# greenhouse_MA_3.net
KiCad netlist of a schematic drawn in Altium Designer
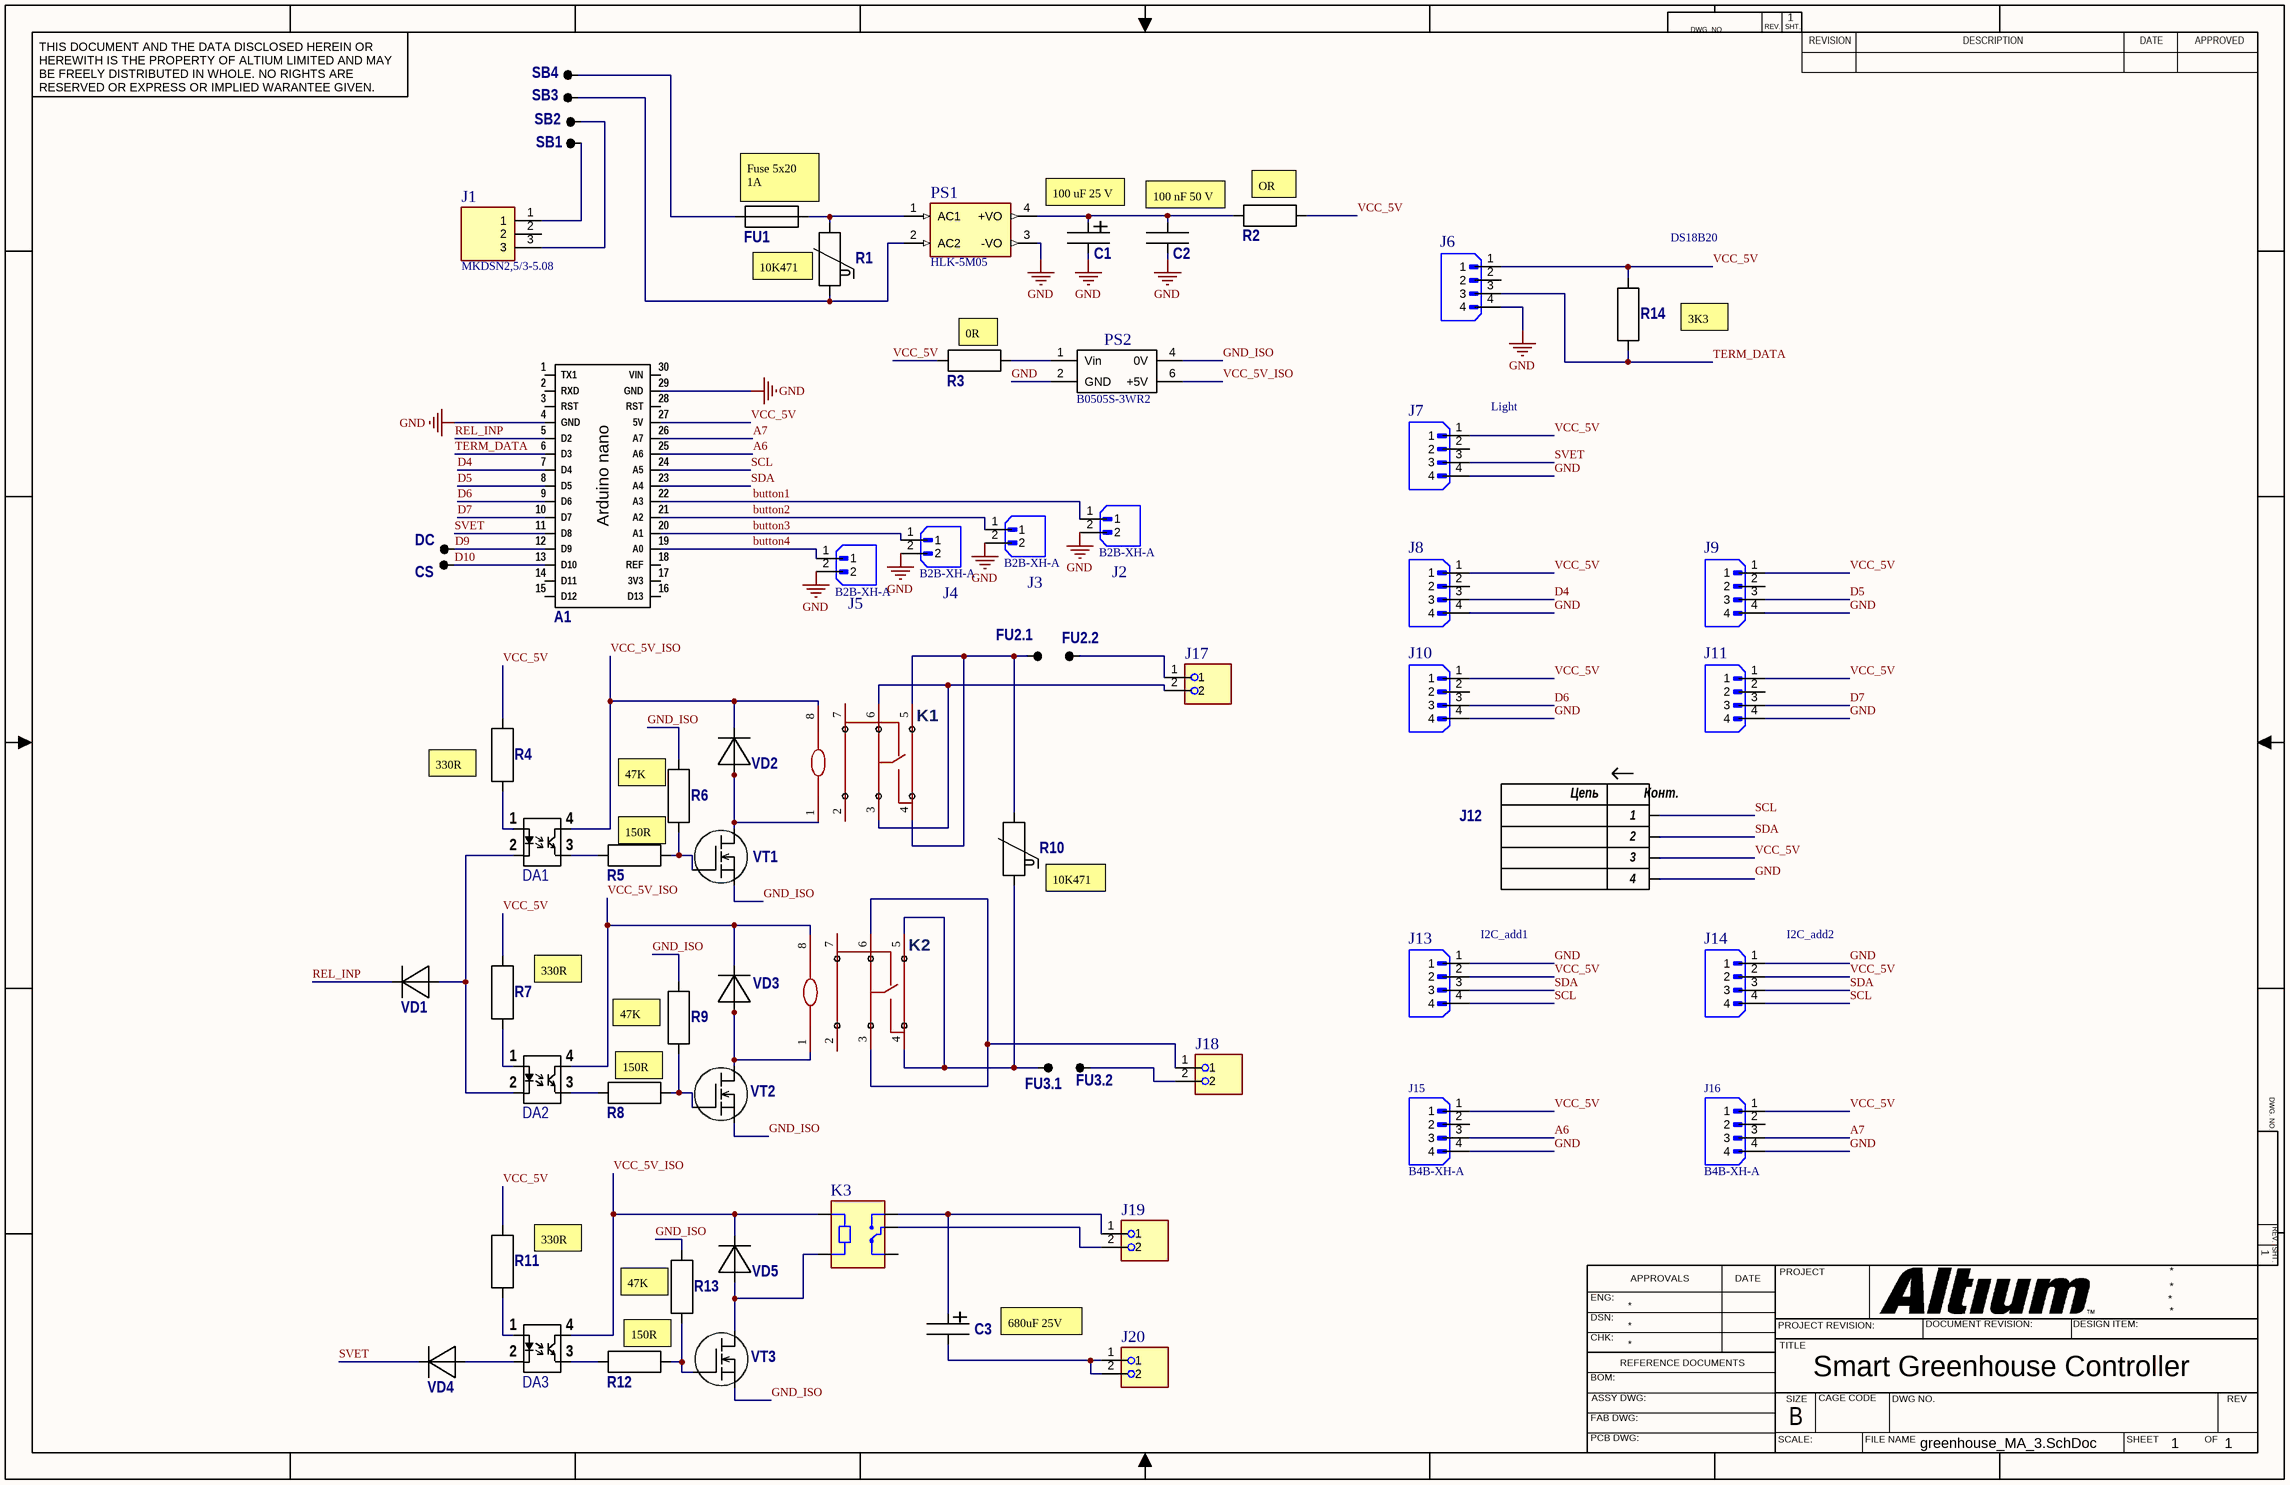
[diagram p0: greenhouse_MA_3.SchDoc]

(export (version "E")
  (design (tool "Eeschema 10.0.6"))
  (components
    (comp (ref "A1")
      (value "Arduino Nano")
      (footprint "Arduino nano")
      (libsource (lib "Microcontroller_V3.4_BVI") (part "Arduino Nano"))
    )
    (comp (ref "C1")
      (value "100uF 25V Electrolytic Capacitor THT Radial")
      (footprint "capr- 2.5D6.5H12")
      (description "Конденсатор алюминиевый радиальный")
      (libsource (lib "RLC V7.1_BVI") (part "C Al R"))
    )
    (comp (ref "C2")
      (value "100nF 50V X7R THT 5mm")
      (footprint "C__s 5-d 5.5-t4")
      (description "Конденсатор керамика")
      (libsource (lib "RLC V7.1_BVI") (part "C_Disk"))
    )
    (comp (ref "C3")
      (value "680uF 25V Electrolytic Capacitor THT Radial")
      (footprint "capr- 3.5D8H20")
      (description "Конденсатор алюминиевый радиальный")
      (libsource (lib "RLC V7.1_BVI") (part "C Al R"))
    )
    (comp (ref "CS")
      (value "Отпайка")
      (footprint "Отпайка 1.2")
      (description "Отпайка для проводника")
      (libsource (lib "RLC V7.1_BVI") (part "Отпайка"))
    )
    (comp (ref "DA1")
      (value "Optocoupler EL817 DIP-4")
      (footprint "DIP-4")
      (description "Оптрон выход - транзистор")
      (libsource (lib "Optocoupler V2.2_BVI") (part "EL817"))
    )
    (comp (ref "DA2")
      (value "Optocoupler EL817 DIP-4")
      (footprint "DIP-4")
      (description "Оптрон выход - транзистор")
      (libsource (lib "Optocoupler V2.2_BVI") (part "EL817"))
    )
    (comp (ref "DA3")
      (value "Optocoupler EL817 DIP-4")
      (footprint "DIP-4")
      (description "Оптрон выход - транзистор")
      (libsource (lib "Optocoupler V2.2_BVI") (part "EL817"))
    )
    (comp (ref "DC")
      (value "Отпайка")
      (footprint "Отпайка 1.2")
      (description "Отпайка для проводника")
      (libsource (lib "RLC V7.1_BVI") (part "Отпайка"))
    )
    (comp (ref "FU1")
      (value "1A slow 5x20 mm")
      (footprint "FU_FC-001-N(DH)")
      (description "Предохранитель плавкий с держателем.")
      (libsource (lib "RLC V7.1_BVI") (part "FU + Clip"))
    )
    (comp (ref "FU2.1")
      (value "Отпайка")
      (footprint "Отпайка 1.5")
      (description "Отпайка для проводника")
      (libsource (lib "RLC V7.1_BVI") (part "Отпайка"))
    )
    (comp (ref "FU2.2")
      (value "Отпайка")
      (footprint "Отпайка 1.5")
      (description "Отпайка для проводника")
      (libsource (lib "RLC V7.1_BVI") (part "Отпайка"))
    )
    (comp (ref "FU3.1")
      (value "Отпайка")
      (footprint "Отпайка 1.5")
      (description "Отпайка для проводника")
      (libsource (lib "RLC V7.1_BVI") (part "Отпайка"))
    )
    (comp (ref "FU3.2")
      (value "Отпайка")
      (footprint "Отпайка 1.5")
      (description "Отпайка для проводника")
      (libsource (lib "RLC V7.1_BVI") (part "Отпайка"))
    )
    (comp (ref "J1")
      (value "MKDSN2,5/3-5.08")
      (footprint "PHOENIX_MKDSN2,5/3-5.08")
      (fields (field (name "MF") "Phoenix Contact"))
      (libsource (lib "MKDSN2_5_3-5.08") (part "MKDSN2,5/3-5.08"))
    )
    (comp (ref "J2")
      (value "B2B-XH-A")
      (footprint "JST_B2B-XH-A")
      (fields (field (name "MF") "{'manufacturer': u'JST Sales America Inc.'}"))
      (libsource (lib "B2B-XH-A") (part "B2B-XH-A"))
    )
    (comp (ref "J3")
      (value "B2B-XH-A")
      (footprint "JST_B2B-XH-A")
      (fields (field (name "MF") "{'manufacturer': u'JST Sales America Inc.'}"))
      (libsource (lib "B2B-XH-A") (part "B2B-XH-A"))
    )
    (comp (ref "J4")
      (value "B2B-XH-A")
      (footprint "JST_B2B-XH-A")
      (fields (field (name "MF") "{'manufacturer': u'JST Sales America Inc.'}"))
      (libsource (lib "B2B-XH-A") (part "B2B-XH-A"))
    )
    (comp (ref "J5")
      (value "B2B-XH-A")
      (footprint "JST_B2B-XH-A")
      (fields (field (name "MF") "{'manufacturer': u'JST Sales America Inc.'}"))
      (libsource (lib "B2B-XH-A") (part "B2B-XH-A"))
    )
    (comp (ref "J6")
      (value "JST B4B-XH-A Connector 1x4 2.5mm THT Vertical")
      (footprint "JST_B4B-XH-A")
      (description "Connector Header Through Hole 4 position 0.098 (2.50mm)")
      (fields (field (name "MF") "JST Sales") (field (name "MP") "B4B-XH-A"))
      (libsource (lib "B4B-XH-A") (part "B4B-XH-A"))
    )
    (comp (ref "J7")
      (value "JST B4B-XH-A Connector 1x4 2.5mm THT Vertical")
      (footprint "JST_B4B-XH-A")
      (description "Connector Header Through Hole 4 position 0.098 (2.50mm)")
      (fields (field (name "MF") "JST Sales") (field (name "MP") "B4B-XH-A"))
      (libsource (lib "B4B-XH-A") (part "B4B-XH-A"))
    )
    (comp (ref "J8")
      (value "JST B4B-XH-A Connector 1x4 2.5mm THT Vertical")
      (footprint "JST_B4B-XH-A")
      (description "Connector Header Through Hole 4 position 0.098 (2.50mm)")
      (fields (field (name "MF") "JST Sales") (field (name "MP") "B4B-XH-A"))
      (libsource (lib "B4B-XH-A") (part "B4B-XH-A"))
    )
    (comp (ref "J9")
      (value "JST B4B-XH-A Connector 1x4 2.5mm THT Vertical")
      (footprint "JST_B4B-XH-A")
      (description "Connector Header Through Hole 4 position 0.098 (2.50mm)")
      (fields (field (name "MF") "JST Sales") (field (name "MP") "B4B-XH-A"))
      (libsource (lib "B4B-XH-A") (part "B4B-XH-A"))
    )
    (comp (ref "J10")
      (value "JST B4B-XH-A Connector 1x4 2.5mm THT Vertical")
      (footprint "JST_B4B-XH-A")
      (description "Connector Header Through Hole 4 position 0.098 (2.50mm)")
      (fields (field (name "MF") "JST Sales") (field (name "MP") "B4B-XH-A"))
      (libsource (lib "B4B-XH-A") (part "B4B-XH-A"))
    )
    (comp (ref "J11")
      (value "JST B4B-XH-A Connector 1x4 2.5mm THT Vertical")
      (footprint "JST_B4B-XH-A")
      (description "Connector Header Through Hole 4 position 0.098 (2.50mm)")
      (fields (field (name "MF") "JST Sales") (field (name "MP") "B4B-XH-A"))
      (libsource (lib "B4B-XH-A") (part "B4B-XH-A"))
    )
    (comp (ref "J12")
      (value "Pin Header 1x4 2.54mm Right Angle THT Male")
      (footprint "KLS1-207-1*04 R")
      (description "Разъём штыревой на плату 2.54мм 1х4 pin")
      (libsource (lib "Connectors V8.3_BVI") (part "Штырь 1* 4  (1)"))
    )
    (comp (ref "J13")
      (value "JST B4B-XH-A Connector 1x4 2.5mm THT Vertical")
      (footprint "JST_B4B-XH-A")
      (description "Connector Header Through Hole 4 position 0.098 (2.50mm)")
      (fields (field (name "MF") "JST Sales") (field (name "MP") "B4B-XH-A"))
      (libsource (lib "B4B-XH-A") (part "B4B-XH-A"))
    )
    (comp (ref "J14")
      (value "JST B4B-XH-A Connector 1x4 2.5mm THT Vertical")
      (footprint "JST_B4B-XH-A")
      (description "Connector Header Through Hole 4 position 0.098 (2.50mm)")
      (fields (field (name "MF") "JST Sales") (field (name "MP") "B4B-XH-A"))
      (libsource (lib "B4B-XH-A") (part "B4B-XH-A"))
    )
    (comp (ref "J15")
      (value "B4B-XH-A")
      (footprint "JST_B4B-XH-A")
      (description "Connector Header Through Hole 4 position 0.098 (2.50mm)")
      (fields (field (name "MF") "JST Sales"))
      (libsource (lib "B4B-XH-A") (part "B4B-XH-A"))
    )
    (comp (ref "J16")
      (value "B4B-XH-A")
      (footprint "JST_B4B-XH-A")
      (description "Connector Header Through Hole 4 position 0.098 (2.50mm)")
      (fields (field (name "MF") "JST Sales"))
      (libsource (lib "B4B-XH-A") (part "B4B-XH-A"))
    )
    (comp (ref "J17")
      (value "Phoenix Contact MKDSN 2,5/2-5.08 Terminal Block 1x2 5.08mm THT")
      (footprint "PHOENIX_1729128")
      (fields (field (name "MF") "Phoenix Contact") (field (name "MP") "1729128"))
      (libsource (lib "MKDSN2_5_2-5.08") (part "1729128"))
    )
    (comp (ref "J18")
      (value "Phoenix Contact MKDSN 2,5/2-5.08 Terminal Block 1x2 5.08mm THT")
      (footprint "PHOENIX_1729128")
      (fields (field (name "MF") "Phoenix Contact") (field (name "MP") "1729128"))
      (libsource (lib "MKDSN2_5_2-5.08") (part "1729128"))
    )
    (comp (ref "J19")
      (value "Phoenix Contact MKDSN 2,5/2-5.08 Terminal Block 1x2 5.08mm THT")
      (footprint "PHOENIX_1729128")
      (fields (field (name "MF") "Phoenix Contact") (field (name "MP") "1729128"))
      (libsource (lib "MKDSN2_5_2-5.08") (part "1729128"))
    )
    (comp (ref "J20")
      (value "Phoenix Contact MKDSN 2,5/2-5.08 Terminal Block 1x2 5.08mm THT")
      (footprint "PHOENIX_1729128")
      (fields (field (name "MF") "Phoenix Contact") (field (name "MP") "1729128"))
      (libsource (lib "MKDSN2_5_2-5.08") (part "1729128"))
    )
    (comp (ref "K1")
      (value "Relay SMIH-05VDC-SL-C 5V 16A THT")
      (footprint "SMIH-5VDC-SL-C")
      (fields (field (name "MANUFACTURER") "松乐") (field (name "MANUFACTURER PART") "SMIH-05VDC-SL-C"))
      (libsource (lib "SMIH-5VDC-SL-C") (part "SMIH-05VDC-SL-C"))
    )
    (comp (ref "K2")
      (value "Relay SMIH-05VDC-SL-C 5V 16A THT")
      (footprint "SMIH-5VDC-SL-C")
      (fields (field (name "MANUFACTURER") "松乐") (field (name "MANUFACTURER PART") "SMIH-05VDC-SL-C"))
      (libsource (lib "SMIH-5VDC-SL-C") (part "SMIH-05VDC-SL-C"))
    )
    (comp (ref "K3")
      (value "Relay SRD-05VDC-SL-C 5V 10A THT")
      (footprint "RELAY_SRD-05VDC-SL-C")
      (fields (field (name "MF") "Songle Relay") (field (name "MP") "SRD-05VDC-SL-C"))
      (libsource (lib "SRD-05VDC-SL-C") (part "SRD-05VDC-SL-C"))
    )
    (comp (ref "PS1")
      (value "HLK-5M05")
      (footprint "CONV_HLK-5M05")
      (description "AC DC 220V to 5V 5W 5Watt Isolated Switching Step-Down Power Supply Module Converter")
      (fields (field (name "MF") "Hi-link"))
      (libsource (lib "HLK-5M05") (part "HLK-5M05"))
    )
    (comp (ref "PS2")
      (value "B0505S-3WR2")
      (footprint "B0505S-2W")
      (description "Изолированный DC-DC преобразователь, вход 5В, выход 5В 3Вт")
      (libsource (lib "B0505S-2W") (part "B0505S-2W"))
    )
    (comp (ref "R1")
      (value "10K471")
      (footprint "var 10D (Т-5мм)")
      (description "Варистор")
      (libsource (lib "RLC V7.1_BVI") (part "RU_1"))
    )
    (comp (ref "R2")
      (value "0R 1% 1206")
      (footprint "Res_1206 3D")
      (description "Резисторы плёночные (SMD; МЛТ; С2-33Н; MP9xxx)")
      (libsource (lib "RLC V7.1_BVI") (part "R"))
    )
    (comp (ref "R3")
      (value "0R 1% 1206")
      (footprint "Res_1206 3D")
      (description "Резисторы плёночные (SMD; МЛТ; С2-33Н; MP9xxx)")
      (libsource (lib "RLC V7.1_BVI") (part "R"))
    )
    (comp (ref "R4")
      (value "330R 1% 1206")
      (footprint "Res_1206 3D")
      (description "Резисторы плёночные (SMD; МЛТ; С2-33Н; MP9xxx)")
      (libsource (lib "RLC V7.1_BVI") (part "R"))
    )
    (comp (ref "R5")
      (value "150R 1% 1206")
      (footprint "Res_1206 3D")
      (description "Резисторы плёночные (SMD; МЛТ; С2-33Н; MP9xxx)")
      (libsource (lib "RLC V7.1_BVI") (part "R"))
    )
    (comp (ref "R6")
      (value "47k 1% 1206")
      (footprint "Res_1206 3D")
      (description "Резисторы плёночные (SMD; МЛТ; С2-33Н; MP9xxx)")
      (libsource (lib "RLC V7.1_BVI") (part "R"))
    )
    (comp (ref "R7")
      (value "330R 1% 1206")
      (footprint "Res_1206 3D")
      (description "Резисторы плёночные (SMD; МЛТ; С2-33Н; MP9xxx)")
      (libsource (lib "RLC V7.1_BVI") (part "R"))
    )
    (comp (ref "R8")
      (value "150R 1% 1206")
      (footprint "Res_1206 3D")
      (description "Резисторы плёночные (SMD; МЛТ; С2-33Н; MP9xxx)")
      (libsource (lib "RLC V7.1_BVI") (part "R"))
    )
    (comp (ref "R9")
      (value "47k 1% 1206")
      (footprint "Res_1206 3D")
      (description "Резисторы плёночные (SMD; МЛТ; С2-33Н; MP9xxx)")
      (libsource (lib "RLC V7.1_BVI") (part "R"))
    )
    (comp (ref "R10")
      (value "10K471")
      (footprint "var 10D (Т-5мм)")
      (description "Варистор")
      (libsource (lib "RLC V7.1_BVI") (part "RU_1"))
    )
    (comp (ref "R11")
      (value "330R 1% 1206")
      (footprint "Res_1206 3D")
      (description "Резисторы плёночные (SMD; МЛТ; С2-33Н; MP9xxx)")
      (libsource (lib "RLC V7.1_BVI") (part "R"))
    )
    (comp (ref "R12")
      (value "150R 1% 1206")
      (footprint "Res_1206 3D")
      (description "Резисторы плёночные (SMD; МЛТ; С2-33Н; MP9xxx)")
      (libsource (lib "RLC V7.1_BVI") (part "R"))
    )
    (comp (ref "R13")
      (value "47k 1% 1206")
      (footprint "Res_1206 3D")
      (description "Резисторы плёночные (SMD; МЛТ; С2-33Н; MP9xxx)")
      (libsource (lib "RLC V7.1_BVI") (part "R"))
    )
    (comp (ref "R14")
      (value "3.3K 1% 1206")
      (footprint "Res_1206 3D")
      (description "Резисторы плёночные (SMD; МЛТ; С2-33Н; MP9xxx)")
      (libsource (lib "RLC V7.1_BVI") (part "R"))
    )
    (comp (ref "SB1")
      (value "Отпайка")
      (footprint "Отпайка 1.2")
      (description "Отпайка для проводника")
      (libsource (lib "Switches V3.4_BVI") (part "Отпайка"))
    )
    (comp (ref "SB2")
      (value "Отпайка")
      (footprint "Отпайка 1.2")
      (description "Отпайка для проводника")
      (libsource (lib "Switches V3.4_BVI") (part "Отпайка"))
    )
    (comp (ref "SB3")
      (value "Отпайка")
      (footprint "Отпайка 1.2")
      (description "Отпайка для проводника")
      (libsource (lib "Switches V3.4_BVI") (part "Отпайка"))
    )
    (comp (ref "SB4")
      (value "Отпайка")
      (footprint "Отпайка 1.2")
      (description "Отпайка для проводника")
      (libsource (lib "Switches V3.4_BVI") (part "Отпайка"))
    )
    (comp (ref "VD1")
      (value "1N4007 1A 1000V Rectifier Diode DO-41")
      (footprint "DO-41  (5.0)")
      (description "Диод  одиночный")
      (libsource (lib "VD_VT_V6.3 BVI") (part "Диод.  x1  (2)"))
    )
    (comp (ref "VD2")
      (value "UF4007 1A 1000V Fast Diode DO-41")
      (footprint "DO-41  (5.0)")
      (description "Диод  одиночный")
      (libsource (lib "VD_VT_V6.3 BVI") (part "Диод.  x1  (2)"))
    )
    (comp (ref "VD3")
      (value "UF4007 1A 1000V Fast Diode DO-41")
      (footprint "DO-41  (5.0)")
      (description "Диод  одиночный")
      (libsource (lib "VD_VT_V6.3 BVI") (part "Диод.  x1  (2)"))
    )
    (comp (ref "VD4")
      (value "1N4007 1A 1000V Rectifier Diode DO-41")
      (footprint "DO-41  (5.0)")
      (description "Диод  одиночный")
      (libsource (lib "VD_VT_V6.3 BVI") (part "Диод.  x1  (2)"))
    )
    (comp (ref "VD5")
      (value "UF4007 1A 1000V Fast Diode DO-41")
      (footprint "DO-41  (5.0)")
      (description "Диод  одиночный")
      (libsource (lib "VD_VT_V6.3 BVI") (part "Диод.  x1  (2)"))
    )
    (comp (ref "VT1")
      (value "IRLML6344")
      (footprint "SOT-23-3")
      (description "Транзистор MOSFET N-канал")
      (libsource (lib "VD_VT_V6.3 BVI") (part "VT MOSFET-N"))
    )
    (comp (ref "VT2")
      (value "IRLML6344")
      (footprint "SOT-23-3")
      (description "Транзистор MOSFET N-канал")
      (libsource (lib "VD_VT_V6.3 BVI") (part "VT MOSFET-N"))
    )
    (comp (ref "VT3")
      (value "IRLML6344")
      (footprint "SOT-23-3")
      (description "Транзистор MOSFET N-канал")
      (libsource (lib "VD_VT_V6.3 BVI") (part "VT MOSFET-N"))
    )
  )
  (nets
    (net (code "1") (name "/A6") (class "Default")
      (node (ref "A1") (pin "25") (pinfunction "A6_25") (pintype "passive"))
      (node (ref "J15") (pin "3") (pinfunction "3_3") (pintype "passive"))
    )
    (net (code "2") (name "/A7") (class "Default")
      (node (ref "A1") (pin "26") (pinfunction "A7_26") (pintype "passive"))
      (node (ref "J16") (pin "3") (pinfunction "3_3") (pintype "passive"))
    )
    (net (code "3") (name "/D4") (class "Default")
      (node (ref "A1") (pin "7") (pinfunction "D4_7") (pintype "passive"))
      (node (ref "J8") (pin "3") (pinfunction "3_3") (pintype "passive"))
    )
    (net (code "4") (name "/D5") (class "Default")
      (node (ref "A1") (pin "8") (pinfunction "D5_8") (pintype "passive"))
      (node (ref "J9") (pin "3") (pinfunction "3_3") (pintype "passive"))
    )
    (net (code "5") (name "/D6") (class "Default")
      (node (ref "A1") (pin "9") (pinfunction "D6_9") (pintype "passive"))
      (node (ref "J10") (pin "3") (pinfunction "3_3") (pintype "passive"))
    )
    (net (code "6") (name "/D7") (class "Default")
      (node (ref "A1") (pin "10") (pinfunction "D7_10") (pintype "passive"))
      (node (ref "J11") (pin "3") (pinfunction "3_3") (pintype "passive"))
    )
    (net (code "7") (name "/D9") (class "Default")
      (node (ref "A1") (pin "12") (pinfunction "D9_12") (pintype "passive"))
      (node (ref "DC") (pin "1") (pintype "passive"))
    )
    (net (code "8") (name "/D10") (class "Default")
      (node (ref "A1") (pin "13") (pinfunction "D10_13") (pintype "passive"))
      (node (ref "CS") (pin "1") (pintype "passive"))
    )
    (net (code "9") (name "/GND_ISO") (class "Default")
      (node (ref "PS2") (pin "4") (pinfunction "0V_4") (pintype "passive"))
      (node (ref "R13") (pin "2") (pintype "passive"))
      (node (ref "R6") (pin "2") (pintype "passive"))
      (node (ref "R9") (pin "2") (pintype "passive"))
      (node (ref "VT1") (pin "3") (pinfunction "S_3") (pintype "passive"))
      (node (ref "VT2") (pin "3") (pinfunction "S_3") (pintype "passive"))
      (node (ref "VT3") (pin "3") (pinfunction "S_3") (pintype "passive"))
    )
    (net (code "10") (name "/REL_INP") (class "Default")
      (node (ref "A1") (pin "5") (pinfunction "D2_5") (pintype "passive"))
      (node (ref "VD1") (pin "1") (pinfunction "K_1") (pintype "passive"))
    )
    (net (code "11") (name "/SCL") (class "Default")
      (node (ref "A1") (pin "24") (pinfunction "A5_24") (pintype "passive"))
      (node (ref "J12") (pin "1") (pintype "passive"))
      (node (ref "J13") (pin "4") (pinfunction "4_4") (pintype "passive"))
      (node (ref "J14") (pin "4") (pinfunction "4_4") (pintype "passive"))
    )
    (net (code "12") (name "/SDA") (class "Default")
      (node (ref "A1") (pin "23") (pinfunction "A4_23") (pintype "passive"))
      (node (ref "J12") (pin "2") (pintype "passive"))
      (node (ref "J13") (pin "3") (pinfunction "3_3") (pintype "passive"))
      (node (ref "J14") (pin "3") (pinfunction "3_3") (pintype "passive"))
    )
    (net (code "13") (name "/SVET") (class "Default")
      (node (ref "A1") (pin "11") (pinfunction "D8_11") (pintype "passive"))
      (node (ref "J7") (pin "3") (pinfunction "3_3") (pintype "passive"))
      (node (ref "VD4") (pin "1") (pinfunction "K_1") (pintype "passive"))
    )
    (net (code "14") (name "/TERM_DATA") (class "Default")
      (node (ref "A1") (pin "6") (pinfunction "D3_6") (pintype "passive"))
      (node (ref "J6") (pin "3") (pinfunction "3_3") (pintype "passive"))
      (node (ref "R14") (pin "1") (pintype "passive"))
    )
    (net (code "15") (name "/VCC_5V") (class "Default")
      (node (ref "A1") (pin "27") (pinfunction "5V_27") (pintype "passive"))
      (node (ref "J10") (pin "1") (pinfunction "1_1") (pintype "passive"))
      (node (ref "J11") (pin "1") (pinfunction "1_1") (pintype "passive"))
      (node (ref "J12") (pin "3") (pintype "passive"))
      (node (ref "J13") (pin "2") (pinfunction "2_2") (pintype "passive"))
      (node (ref "J14") (pin "2") (pinfunction "2_2") (pintype "passive"))
      (node (ref "J15") (pin "1") (pinfunction "1_1") (pintype "passive"))
      (node (ref "J16") (pin "1") (pinfunction "1_1") (pintype "passive"))
      (node (ref "J6") (pin "1") (pinfunction "1_1") (pintype "passive"))
      (node (ref "J7") (pin "1") (pinfunction "1_1") (pintype "passive"))
      (node (ref "J8") (pin "1") (pinfunction "1_1") (pintype "passive"))
      (node (ref "J9") (pin "1") (pinfunction "1_1") (pintype "passive"))
      (node (ref "R11") (pin "2") (pintype "passive"))
      (node (ref "R14") (pin "2") (pintype "passive"))
      (node (ref "R2") (pin "1") (pintype "passive"))
      (node (ref "R3") (pin "2") (pintype "passive"))
      (node (ref "R4") (pin "2") (pintype "passive"))
      (node (ref "R7") (pin "2") (pintype "passive"))
    )
    (net (code "16") (name "/VCC_5V_ISO") (class "Default")
      (node (ref "DA1") (pin "4") (pinfunction "C_4") (pintype "passive"))
      (node (ref "DA2") (pin "4") (pinfunction "C_4") (pintype "passive"))
      (node (ref "DA3") (pin "4") (pinfunction "C_4") (pintype "passive"))
      (node (ref "K1") (pin "8") (pinfunction "8_8") (pintype "passive"))
      (node (ref "K2") (pin "8") (pinfunction "8_8") (pintype "passive"))
      (node (ref "K3") (pin "A1") (pinfunction "A1_A1") (pintype "passive"))
      (node (ref "PS2") (pin "6") (pinfunction "+5V_6") (pintype "passive"))
      (node (ref "VD2") (pin "1") (pinfunction "K_1") (pintype "passive"))
      (node (ref "VD3") (pin "1") (pinfunction "K_1") (pintype "passive"))
      (node (ref "VD5") (pin "1") (pinfunction "K_1") (pintype "passive"))
    )
    (net (code "17") (name "/button1") (class "Default")
      (node (ref "A1") (pin "22") (pinfunction "A3_22") (pintype "passive"))
      (node (ref "J2") (pin "1") (pinfunction "1_1") (pintype "passive"))
    )
    (net (code "18") (name "/button2") (class "Default")
      (node (ref "A1") (pin "21") (pinfunction "A2_21") (pintype "passive"))
      (node (ref "J3") (pin "1") (pinfunction "1_1") (pintype "passive"))
    )
    (net (code "19") (name "/button3") (class "Default")
      (node (ref "A1") (pin "20") (pinfunction "A1_20") (pintype "passive"))
      (node (ref "J4") (pin "1") (pinfunction "1_1") (pintype "passive"))
    )
    (net (code "20") (name "/button4") (class "Default")
      (node (ref "A1") (pin "19") (pinfunction "A0_19") (pintype "passive"))
      (node (ref "J5") (pin "1") (pinfunction "1_1") (pintype "passive"))
    )
    (net (code "21") (name "GND") (class "Default")
      (node (ref "A1") (pin "29") (pinfunction "GND_29") (pintype "passive"))
      (node (ref "A1") (pin "4") (pinfunction "GND_4") (pintype "passive"))
      (node (ref "C1") (pin "1") (pinfunction "-_1") (pintype "passive"))
      (node (ref "C2") (pin "2") (pintype "passive"))
      (node (ref "J10") (pin "4") (pinfunction "4_4") (pintype "passive"))
      (node (ref "J11") (pin "4") (pinfunction "4_4") (pintype "passive"))
      (node (ref "J12") (pin "4") (pintype "passive"))
      (node (ref "J13") (pin "1") (pinfunction "1_1") (pintype "passive"))
      (node (ref "J14") (pin "1") (pinfunction "1_1") (pintype "passive"))
      (node (ref "J15") (pin "4") (pinfunction "4_4") (pintype "passive"))
      (node (ref "J16") (pin "4") (pinfunction "4_4") (pintype "passive"))
      (node (ref "J2") (pin "2") (pinfunction "2_2") (pintype "passive"))
      (node (ref "J3") (pin "2") (pinfunction "2_2") (pintype "passive"))
      (node (ref "J4") (pin "2") (pinfunction "2_2") (pintype "passive"))
      (node (ref "J5") (pin "2") (pinfunction "2_2") (pintype "passive"))
      (node (ref "J6") (pin "4") (pinfunction "4_4") (pintype "passive"))
      (node (ref "J7") (pin "4") (pinfunction "4_4") (pintype "passive"))
      (node (ref "J8") (pin "4") (pinfunction "4_4") (pintype "passive"))
      (node (ref "J9") (pin "4") (pinfunction "4_4") (pintype "passive"))
      (node (ref "PS1") (pin "3") (pinfunction "-VO_3") (pintype "output"))
      (node (ref "PS2") (pin "2") (pinfunction "GND_2") (pintype "passive"))
    )
    (net (code "22") (name "Net-(C1-+)") (class "Default")
      (node (ref "C1") (pin "2") (pinfunction "+_2") (pintype "passive"))
      (node (ref "C2") (pin "1") (pintype "passive"))
      (node (ref "PS1") (pin "4") (pinfunction "+VO_4") (pintype "output"))
      (node (ref "R2") (pin "2") (pintype "passive"))
    )
    (net (code "23") (name "Net-(C3-+)") (class "Default")
      (node (ref "C3") (pin "2") (pinfunction "+_2") (pintype "passive"))
      (node (ref "J19") (pin "1") (pinfunction "1_1") (pintype "passive"))
      (node (ref "K3") (pin "NO") (pinfunction "NO_NO") (pintype "passive"))
    )
    (net (code "24") (name "Net-(C3--)") (class "Default")
      (node (ref "C3") (pin "1") (pinfunction "-_1") (pintype "passive"))
      (node (ref "J20") (pin "1") (pinfunction "1_1") (pintype "passive"))
      (node (ref "J20") (pin "2") (pinfunction "2_2") (pintype "passive"))
    )
    (net (code "25") (name "Net-(DA1-E)") (class "Default")
      (node (ref "DA1") (pin "3") (pinfunction "E_3") (pintype "passive"))
      (node (ref "R5") (pin "1") (pintype "passive"))
    )
    (net (code "26") (name "Net-(DA1-Led_A)") (class "Default")
      (node (ref "DA1") (pin "1") (pinfunction "Led_A_1") (pintype "passive"))
      (node (ref "R4") (pin "1") (pintype "passive"))
    )
    (net (code "27") (name "Net-(DA1-Led_C)") (class "Default")
      (node (ref "DA1") (pin "2") (pinfunction "Led_C_2") (pintype "passive"))
      (node (ref "DA2") (pin "2") (pinfunction "Led_C_2") (pintype "passive"))
      (node (ref "VD1") (pin "2") (pinfunction "A_2") (pintype "passive"))
    )
    (net (code "28") (name "Net-(DA2-E)") (class "Default")
      (node (ref "DA2") (pin "3") (pinfunction "E_3") (pintype "passive"))
      (node (ref "R8") (pin "1") (pintype "passive"))
    )
    (net (code "29") (name "Net-(DA2-Led_A)") (class "Default")
      (node (ref "DA2") (pin "1") (pinfunction "Led_A_1") (pintype "passive"))
      (node (ref "R7") (pin "1") (pintype "passive"))
    )
    (net (code "30") (name "Net-(DA3-E)") (class "Default")
      (node (ref "DA3") (pin "3") (pinfunction "E_3") (pintype "passive"))
      (node (ref "R12") (pin "1") (pintype "passive"))
    )
    (net (code "31") (name "Net-(DA3-Led_A)") (class "Default")
      (node (ref "DA3") (pin "1") (pinfunction "Led_A_1") (pintype "passive"))
      (node (ref "R11") (pin "1") (pintype "passive"))
    )
    (net (code "32") (name "Net-(DA3-Led_C)") (class "Default")
      (node (ref "DA3") (pin "2") (pinfunction "Led_C_2") (pintype "passive"))
      (node (ref "VD4") (pin "2") (pinfunction "A_2") (pintype "passive"))
    )
    (net (code "33") (name "Net-(FU1-Pad1)") (class "Default")
      (node (ref "FU1") (pin "1") (pintype "passive"))
      (node (ref "SB4") (pin "1") (pintype "passive"))
    )
    (net (code "34") (name "Net-(FU2.1-Pad1)") (class "Default")
      (node (ref "FU2.1") (pin "1") (pintype "passive"))
      (node (ref "K1") (pin "4") (pinfunction "4_4") (pintype "passive"))
      (node (ref "K1") (pin "5") (pinfunction "5_5") (pintype "passive"))
      (node (ref "R10") (pin "2") (pintype "passive"))
    )
    (net (code "35") (name "Net-(FU2.2-Pad1)") (class "Default")
      (node (ref "FU2.2") (pin "1") (pintype "passive"))
      (node (ref "J17") (pin "1") (pinfunction "1_1") (pintype "passive"))
    )
    (net (code "36") (name "Net-(FU3.1-Pad1)") (class "Default")
      (node (ref "FU3.1") (pin "1") (pintype "passive"))
      (node (ref "K2") (pin "4") (pinfunction "4_4") (pintype "passive"))
      (node (ref "K2") (pin "5") (pinfunction "5_5") (pintype "passive"))
      (node (ref "R10") (pin "1") (pintype "passive"))
    )
    (net (code "37") (name "Net-(FU3.2-Pad1)") (class "Default")
      (node (ref "FU3.2") (pin "1") (pintype "passive"))
      (node (ref "J18") (pin "2") (pinfunction "2_2") (pintype "passive"))
    )
    (net (code "38") (name "Net-(J1-Pad1)") (class "Default")
      (node (ref "J1") (pin "1") (pinfunction "1_1") (pintype "passive"))
      (node (ref "SB1") (pin "1") (pintype "passive"))
    )
    (net (code "39") (name "Net-(J1-Pad3)") (class "Default")
      (node (ref "J1") (pin "3") (pinfunction "3_3") (pintype "passive"))
      (node (ref "SB2") (pin "1") (pintype "passive"))
    )
    (net (code "40") (name "Net-(J17-Pad2)") (class "Default")
      (node (ref "J17") (pin "2") (pinfunction "2_2") (pintype "passive"))
      (node (ref "K1") (pin "3") (pinfunction "3_3") (pintype "passive"))
      (node (ref "K1") (pin "6") (pinfunction "6_6") (pintype "passive"))
    )
    (net (code "41") (name "Net-(J18-Pad1)") (class "Default")
      (node (ref "J18") (pin "1") (pinfunction "1_1") (pintype "passive"))
      (node (ref "K2") (pin "3") (pinfunction "3_3") (pintype "passive"))
      (node (ref "K2") (pin "6") (pinfunction "6_6") (pintype "passive"))
    )
    (net (code "42") (name "Net-(J19-Pad2)") (class "Default")
      (node (ref "J19") (pin "2") (pinfunction "2_2") (pintype "passive"))
      (node (ref "K3") (pin "COM") (pinfunction "COM_COM") (pintype "passive"))
    )
    (net (code "43") (name "Net-(PS1-AC1)") (class "Default")
      (node (ref "FU1") (pin "2") (pintype "passive"))
      (node (ref "PS1") (pin "1") (pinfunction "AC1_1") (pintype "input"))
      (node (ref "R1") (pin "2") (pintype "passive"))
    )
    (net (code "44") (name "Net-(PS1-AC2)") (class "Default")
      (node (ref "PS1") (pin "2") (pinfunction "AC2_2") (pintype "input"))
      (node (ref "R1") (pin "1") (pintype "passive"))
      (node (ref "SB3") (pin "1") (pintype "passive"))
    )
    (net (code "45") (name "Net-(PS2-Vin)") (class "Default")
      (node (ref "PS2") (pin "1") (pinfunction "Vin_1") (pintype "passive"))
      (node (ref "R3") (pin "1") (pintype "passive"))
    )
    (net (code "46") (name "Net-(VD2-A)") (class "Default")
      (node (ref "K1") (pin "1") (pinfunction "1_1") (pintype "passive"))
      (node (ref "VD2") (pin "2") (pinfunction "A_2") (pintype "passive"))
      (node (ref "VT1") (pin "2") (pinfunction "D_2") (pintype "passive"))
    )
    (net (code "47") (name "Net-(VD3-A)") (class "Default")
      (node (ref "K2") (pin "1") (pinfunction "1_1") (pintype "passive"))
      (node (ref "VD3") (pin "2") (pinfunction "A_2") (pintype "passive"))
      (node (ref "VT2") (pin "2") (pinfunction "D_2") (pintype "passive"))
    )
    (net (code "48") (name "Net-(VD5-A)") (class "Default")
      (node (ref "K3") (pin "A2") (pinfunction "A2_A2") (pintype "passive"))
      (node (ref "VD5") (pin "2") (pinfunction "A_2") (pintype "passive"))
      (node (ref "VT3") (pin "2") (pinfunction "D_2") (pintype "passive"))
    )
    (net (code "49") (name "Net-(VT1-G)") (class "Default")
      (node (ref "R5") (pin "2") (pintype "passive"))
      (node (ref "R6") (pin "1") (pintype "passive"))
      (node (ref "VT1") (pin "1") (pinfunction "G_1") (pintype "passive"))
    )
    (net (code "50") (name "Net-(VT2-G)") (class "Default")
      (node (ref "R8") (pin "2") (pintype "passive"))
      (node (ref "R9") (pin "1") (pintype "passive"))
      (node (ref "VT2") (pin "1") (pinfunction "G_1") (pintype "passive"))
    )
    (net (code "51") (name "Net-(VT3-G)") (class "Default")
      (node (ref "R12") (pin "2") (pintype "passive"))
      (node (ref "R13") (pin "1") (pintype "passive"))
      (node (ref "VT3") (pin "1") (pinfunction "G_1") (pintype "passive"))
    )
    (net (code "52") (name "unconnected-(A1-3V3-Pad17)") (class "Default")
      (node (ref "A1") (pin "17") (pinfunction "3V3_17") (pintype "passive"))
    )
    (net (code "53") (name "unconnected-(A1-D11-Pad14)") (class "Default")
      (node (ref "A1") (pin "14") (pinfunction "D11_14") (pintype "passive"))
    )
    (net (code "54") (name "unconnected-(A1-D12-Pad15)") (class "Default")
      (node (ref "A1") (pin "15") (pinfunction "D12_15") (pintype "passive"))
    )
    (net (code "55") (name "unconnected-(A1-D13-Pad16)") (class "Default")
      (node (ref "A1") (pin "16") (pinfunction "D13_16") (pintype "passive"))
    )
    (net (code "56") (name "unconnected-(A1-REF-Pad18)") (class "Default")
      (node (ref "A1") (pin "18") (pinfunction "REF_18") (pintype "passive"))
    )
    (net (code "57") (name "unconnected-(A1-RST-Pad3)") (class "Default")
      (node (ref "A1") (pin "3") (pinfunction "RST_3") (pintype "passive"))
    )
    (net (code "58") (name "unconnected-(A1-RST-Pad28)") (class "Default")
      (node (ref "A1") (pin "28") (pinfunction "RST_28") (pintype "passive"))
    )
    (net (code "59") (name "unconnected-(A1-RXD-Pad2)") (class "Default")
      (node (ref "A1") (pin "2") (pinfunction "RXD_2") (pintype "passive"))
    )
    (net (code "60") (name "unconnected-(A1-TX1-Pad1)") (class "Default")
      (node (ref "A1") (pin "1") (pinfunction "TX1_1") (pintype "passive"))
    )
    (net (code "61") (name "unconnected-(A1-VIN-Pad30)") (class "Default")
      (node (ref "A1") (pin "30") (pinfunction "VIN_30") (pintype "passive"))
    )
    (net (code "62") (name "unconnected-(J1-Pad2)") (class "Default")
      (node (ref "J1") (pin "2") (pinfunction "2_2") (pintype "passive"))
    )
    (net (code "63") (name "unconnected-(J6-Pad2)") (class "Default")
      (node (ref "J6") (pin "2") (pinfunction "2_2") (pintype "passive"))
    )
    (net (code "64") (name "unconnected-(J7-Pad2)") (class "Default")
      (node (ref "J7") (pin "2") (pinfunction "2_2") (pintype "passive"))
    )
    (net (code "65") (name "unconnected-(J8-Pad2)") (class "Default")
      (node (ref "J8") (pin "2") (pinfunction "2_2") (pintype "passive"))
    )
    (net (code "66") (name "unconnected-(J9-Pad2)") (class "Default")
      (node (ref "J9") (pin "2") (pinfunction "2_2") (pintype "passive"))
    )
    (net (code "67") (name "unconnected-(J10-Pad2)") (class "Default")
      (node (ref "J10") (pin "2") (pinfunction "2_2") (pintype "passive"))
    )
    (net (code "68") (name "unconnected-(J11-Pad2)") (class "Default")
      (node (ref "J11") (pin "2") (pinfunction "2_2") (pintype "passive"))
    )
    (net (code "69") (name "unconnected-(J15-Pad2)") (class "Default")
      (node (ref "J15") (pin "2") (pinfunction "2_2") (pintype "passive"))
    )
    (net (code "70") (name "unconnected-(J16-Pad2)") (class "Default")
      (node (ref "J16") (pin "2") (pinfunction "2_2") (pintype "passive"))
    )
    (net (code "71") (name "unconnected-(K1-Pad2)") (class "Default")
      (node (ref "K1") (pin "2") (pinfunction "2_2") (pintype "passive"))
    )
    (net (code "72") (name "unconnected-(K1-Pad7)") (class "Default")
      (node (ref "K1") (pin "7") (pinfunction "7_7") (pintype "passive"))
    )
    (net (code "73") (name "unconnected-(K2-Pad2)") (class "Default")
      (node (ref "K2") (pin "2") (pinfunction "2_2") (pintype "passive"))
    )
    (net (code "74") (name "unconnected-(K2-Pad7)") (class "Default")
      (node (ref "K2") (pin "7") (pinfunction "7_7") (pintype "passive"))
    )
    (net (code "75") (name "unconnected-(K3-PadNC)") (class "Default")
      (node (ref "K3") (pin "NC") (pinfunction "NC_NC") (pintype "passive"))
    )
  )
)
